# rfm12square.net
KiCad netlist of a schematic drawn in EAGLE
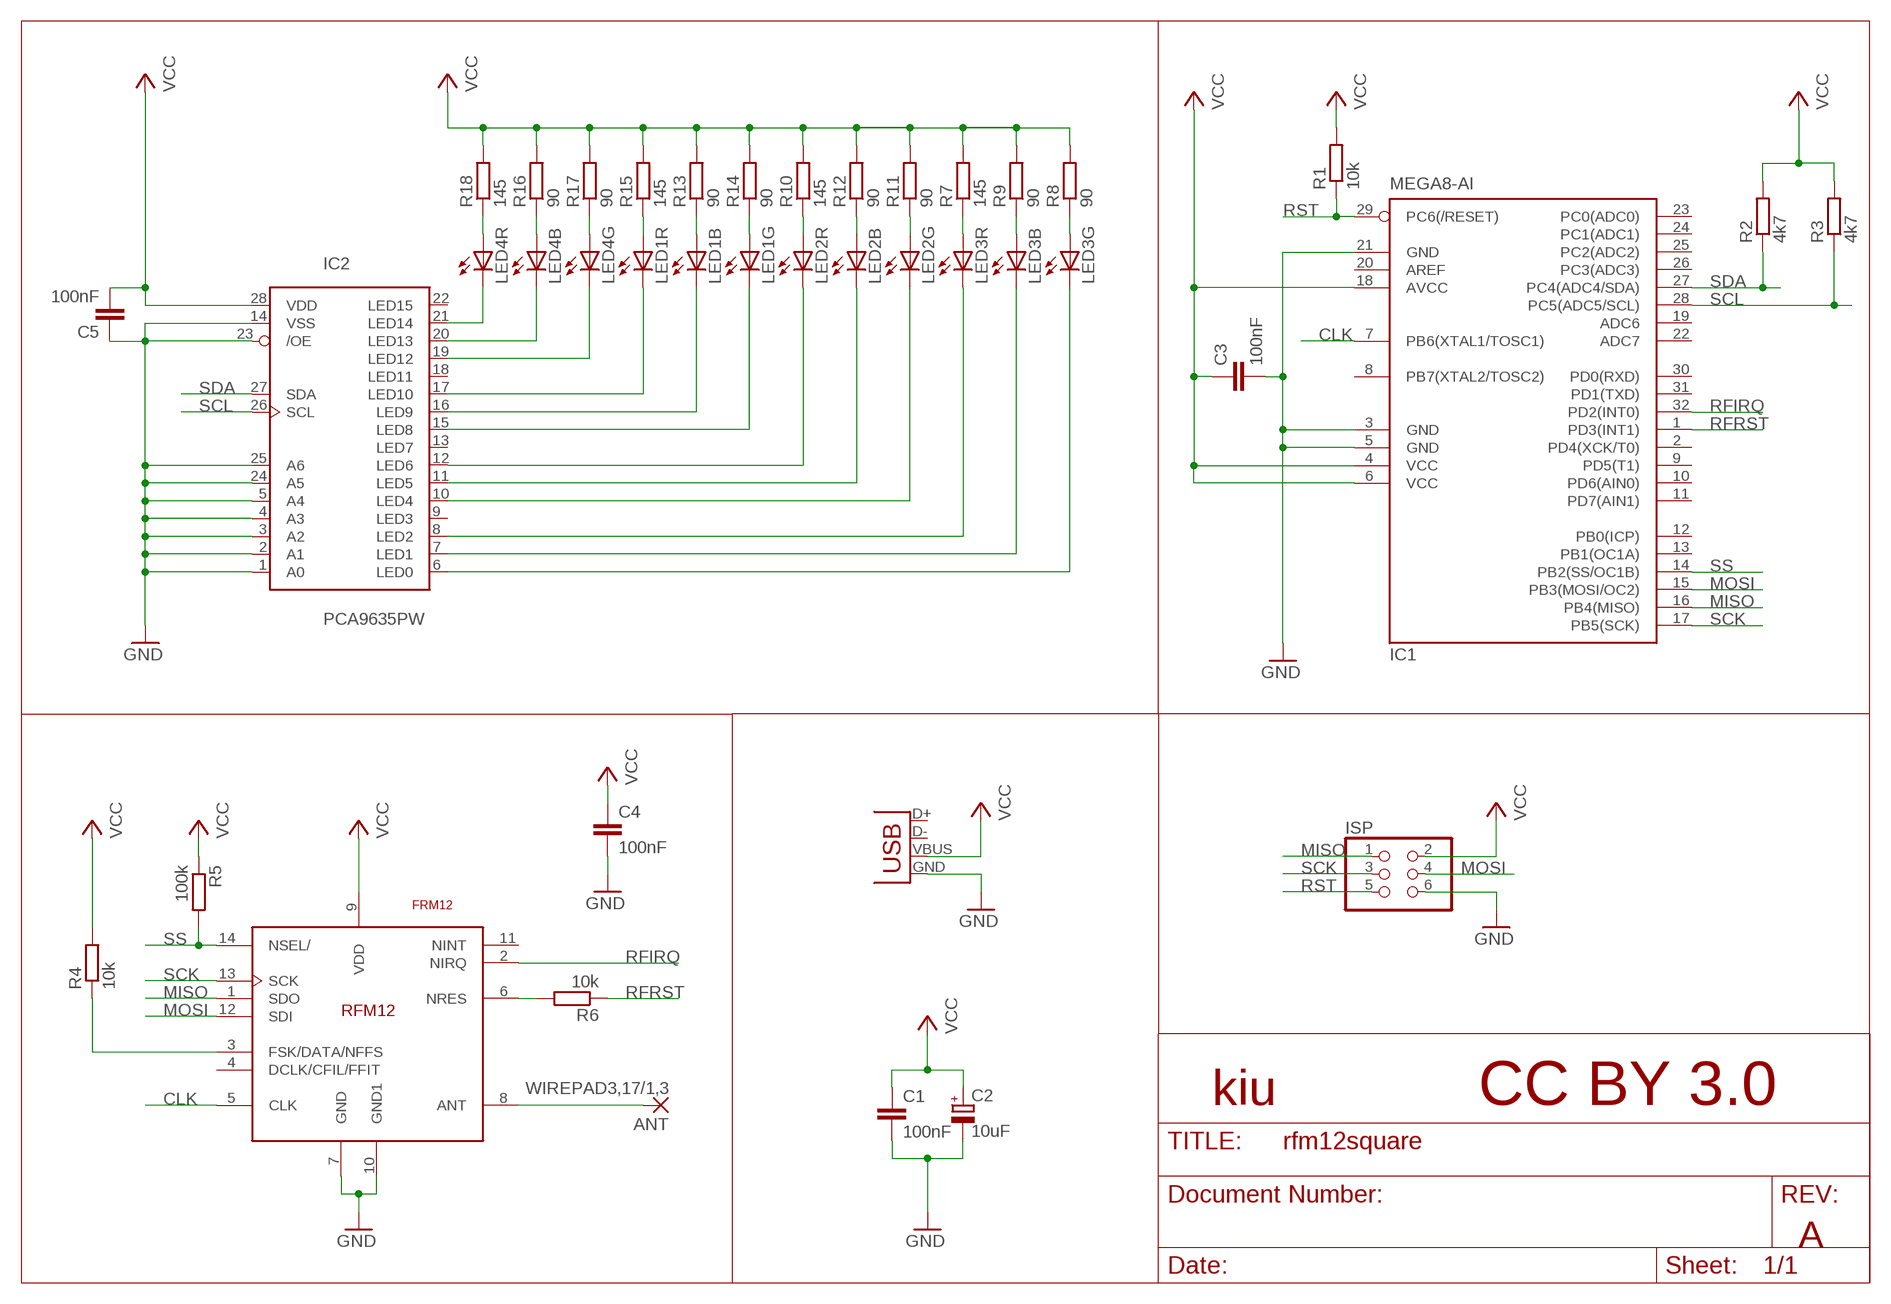
[diagram p0: schematic, sheet 1]

(export (version "E")
  (design (tool "Eeschema 10.0.6"))
  (components
    (comp (ref "ANT")
      (value "WIREPAD3,17/1,3")
      (footprint "eagle-import:3,17_1,3")
      (libsource (lib "eagle-import") (part "WIREPAD3,17/1,3"))
    )
    (comp (ref "C1")
      (value "100nF")
      (footprint "eagle-import:C0603")
      (libsource (lib "eagle-import") (part "C-EUC0603"))
    )
    (comp (ref "C2")
      (value "10uF")
      (footprint "eagle-import:CT3216")
      (libsource (lib "eagle-import") (part "CPOL-EUCT3216"))
    )
    (comp (ref "C3")
      (value "100nF")
      (footprint "eagle-import:C0603")
      (libsource (lib "eagle-import") (part "C-EUC0603"))
    )
    (comp (ref "C4")
      (value "100nF")
      (footprint "eagle-import:C0603")
      (libsource (lib "eagle-import") (part "C-EUC0603"))
    )
    (comp (ref "C5")
      (value "100nF")
      (footprint "eagle-import:C0603")
      (libsource (lib "eagle-import") (part "C-EUC0603"))
    )
    (comp (ref "IC1")
      (value "MEGA8-AI")
      (footprint "eagle-import:TQFP32-08")
      (fields (field (name "MPN") "ATMEGA8-16AU"))
      (libsource (lib "eagle-import") (part "MEGA8-AI"))
    )
    (comp (ref "IC2")
      (value "PCA9635PW")
      (footprint "eagle-import:TSSOP28")
      (libsource (lib "eagle-import") (part "PCA9635PW"))
    )
    (comp (ref "ISP")
      (value "PINHD-2X3")
      (footprint "eagle-import:2X03")
      (libsource (lib "eagle-import") (part "PINHD-2X3"))
    )
    (comp (ref "LED1")
      (value "MULTILED_LRTB_G6TG")
      (footprint "eagle-import:P-LCC-6_TOPLED")
      (libsource (lib "eagle-import") (part "MULTILED_LRTB_G6TG"))
    )
    (comp (ref "LED2")
      (value "MULTILED_LRTB_G6TG")
      (footprint "eagle-import:P-LCC-6_TOPLED")
      (libsource (lib "eagle-import") (part "MULTILED_LRTB_G6TG"))
    )
    (comp (ref "LED3")
      (value "MULTILED_LRTB_G6TG")
      (footprint "eagle-import:P-LCC-6_TOPLED")
      (libsource (lib "eagle-import") (part "MULTILED_LRTB_G6TG"))
    )
    (comp (ref "LED4")
      (value "MULTILED_LRTB_G6TG")
      (footprint "eagle-import:P-LCC-6_TOPLED")
      (libsource (lib "eagle-import") (part "MULTILED_LRTB_G6TG"))
    )
    (comp (ref "R1")
      (value "10k")
      (footprint "eagle-import:R0603")
      (libsource (lib "eagle-import") (part "R-EU_R0603"))
    )
    (comp (ref "R2")
      (value "4k7")
      (footprint "eagle-import:R0603")
      (libsource (lib "eagle-import") (part "R-EU_R0603"))
    )
    (comp (ref "R3")
      (value "4k7")
      (footprint "eagle-import:R0603")
      (libsource (lib "eagle-import") (part "R-EU_R0603"))
    )
    (comp (ref "R4")
      (value "10k")
      (footprint "eagle-import:R0603")
      (libsource (lib "eagle-import") (part "R-EU_R0603"))
    )
    (comp (ref "R5")
      (value "100k")
      (footprint "eagle-import:R0603")
      (libsource (lib "eagle-import") (part "R-EU_R0603"))
    )
    (comp (ref "R6")
      (value "10k")
      (footprint "eagle-import:R0603")
      (libsource (lib "eagle-import") (part "R-EU_R0603"))
    )
    (comp (ref "R7")
      (value "145")
      (footprint "eagle-import:R0603")
      (libsource (lib "eagle-import") (part "R-EU_R0603"))
    )
    (comp (ref "R8")
      (value "90")
      (footprint "eagle-import:R0603")
      (libsource (lib "eagle-import") (part "R-EU_R0603"))
    )
    (comp (ref "R9")
      (value "90")
      (footprint "eagle-import:R0603")
      (libsource (lib "eagle-import") (part "R-EU_R0603"))
    )
    (comp (ref "R10")
      (value "145")
      (footprint "eagle-import:R0603")
      (libsource (lib "eagle-import") (part "R-EU_R0603"))
    )
    (comp (ref "R11")
      (value "90")
      (footprint "eagle-import:R0603")
      (libsource (lib "eagle-import") (part "R-EU_R0603"))
    )
    (comp (ref "R12")
      (value "90")
      (footprint "eagle-import:R0603")
      (libsource (lib "eagle-import") (part "R-EU_R0603"))
    )
    (comp (ref "R13")
      (value "90")
      (footprint "eagle-import:R0603")
      (libsource (lib "eagle-import") (part "R-EU_R0603"))
    )
    (comp (ref "R14")
      (value "90")
      (footprint "eagle-import:R0603")
      (libsource (lib "eagle-import") (part "R-EU_R0603"))
    )
    (comp (ref "R15")
      (value "145")
      (footprint "eagle-import:R0603")
      (libsource (lib "eagle-import") (part "R-EU_R0603"))
    )
    (comp (ref "R16")
      (value "90")
      (footprint "eagle-import:R0603")
      (libsource (lib "eagle-import") (part "R-EU_R0603"))
    )
    (comp (ref "R17")
      (value "90")
      (footprint "eagle-import:R0603")
      (libsource (lib "eagle-import") (part "R-EU_R0603"))
    )
    (comp (ref "R18")
      (value "145")
      (footprint "eagle-import:R0603")
      (libsource (lib "eagle-import") (part "R-EU_R0603"))
    )
    (comp (ref "U$1")
      (value "FRM12")
      (footprint "eagle-import:RFM12")
      (libsource (lib "eagle-import") (part "FRM12"))
    )
    (comp (ref "X1")
      (value "USB-MICROB")
      (footprint "eagle-import:USB-MICROB")
      (libsource (lib "eagle-import") (part "USB-MICROB"))
    )
  )
  (nets
    (net (code "1") (name "/CLK") (class "Default")
      (node (ref "IC1") (pin "7") (pinfunction "PB6(XTAL1/TOSC1)_7") (pintype "bidirectional"))
      (node (ref "U$1") (pin "5") (pinfunction "CLK_5") (pintype "output"))
    )
    (net (code "2") (name "/MISO") (class "Default")
      (node (ref "IC1") (pin "16") (pinfunction "PB4(MISO)_16") (pintype "bidirectional"))
      (node (ref "ISP") (pin "1") (pinfunction "1_1") (pintype "passive"))
      (node (ref "U$1") (pin "1") (pinfunction "SDO_1") (pintype "output"))
    )
    (net (code "3") (name "/MOSI") (class "Default")
      (node (ref "IC1") (pin "15") (pinfunction "PB3(MOSI/OC2)_15") (pintype "bidirectional"))
      (node (ref "ISP") (pin "4") (pinfunction "4_4") (pintype "passive"))
      (node (ref "U$1") (pin "12") (pinfunction "SDI_12") (pintype "input"))
    )
    (net (code "4") (name "/RFIRQ") (class "Default")
      (node (ref "IC1") (pin "32") (pinfunction "PD2(INT0)_32") (pintype "bidirectional"))
      (node (ref "U$1") (pin "2") (pinfunction "NIRQ_2") (pintype "output"))
    )
    (net (code "5") (name "/RFRST") (class "Default")
      (node (ref "IC1") (pin "1") (pinfunction "PD3(INT1)_1") (pintype "bidirectional"))
      (node (ref "R6") (pin "1") (pinfunction "1_1") (pintype "passive"))
    )
    (net (code "6") (name "/RST") (class "Default")
      (node (ref "IC1") (pin "29") (pinfunction "PC6(/RESET)_29") (pintype "bidirectional"))
      (node (ref "ISP") (pin "5") (pinfunction "5_5") (pintype "passive"))
      (node (ref "R1") (pin "1") (pinfunction "1_1") (pintype "passive"))
    )
    (net (code "7") (name "/SCK") (class "Default")
      (node (ref "IC1") (pin "17") (pinfunction "PB5(SCK)_17") (pintype "bidirectional"))
      (node (ref "ISP") (pin "3") (pinfunction "3_3") (pintype "passive"))
      (node (ref "U$1") (pin "13") (pinfunction "SCK_13") (pintype "input"))
    )
    (net (code "8") (name "/SCL") (class "Default")
      (node (ref "IC1") (pin "28") (pinfunction "PC5(ADC5/SCL)_28") (pintype "bidirectional"))
      (node (ref "IC2") (pin "26") (pinfunction "SCL_26") (pintype "input"))
      (node (ref "R3") (pin "1") (pinfunction "1_1") (pintype "passive"))
    )
    (net (code "9") (name "/SDA") (class "Default")
      (node (ref "IC1") (pin "27") (pinfunction "PC4(ADC4/SDA)_27") (pintype "bidirectional"))
      (node (ref "IC2") (pin "27") (pinfunction "SDA_27") (pintype "bidirectional"))
      (node (ref "R2") (pin "1") (pinfunction "1_1") (pintype "passive"))
    )
    (net (code "10") (name "/SS") (class "Default")
      (node (ref "IC1") (pin "14") (pinfunction "PB2(SS/OC1B)_14") (pintype "bidirectional"))
      (node (ref "R5") (pin "2") (pinfunction "2_2") (pintype "passive"))
      (node (ref "U$1") (pin "14") (pinfunction "NSEL/_14") (pintype "input"))
    )
    (net (code "11") (name "GND") (class "Default")
      (node (ref "C1") (pin "2") (pinfunction "2_2") (pintype "passive"))
      (node (ref "C2") (pin "-") (pinfunction "-_-") (pintype "passive"))
      (node (ref "C3") (pin "2") (pinfunction "2_2") (pintype "passive"))
      (node (ref "C4") (pin "2") (pinfunction "2_2") (pintype "passive"))
      (node (ref "C5") (pin "1") (pinfunction "1_1") (pintype "passive"))
      (node (ref "IC1") (pin "21") (pinfunction "GND_21") (pintype "power_in"))
      (node (ref "IC1") (pin "3") (pinfunction "GND_3") (pintype "power_in"))
      (node (ref "IC1") (pin "5") (pinfunction "GND_5") (pintype "power_in"))
      (node (ref "IC2") (pin "1") (pinfunction "A0_1") (pintype "input"))
      (node (ref "IC2") (pin "14") (pinfunction "VSS_14") (pintype "power_in"))
      (node (ref "IC2") (pin "2") (pinfunction "A1_2") (pintype "input"))
      (node (ref "IC2") (pin "23") (pinfunction "/OE_23") (pintype "input"))
      (node (ref "IC2") (pin "24") (pinfunction "A5_24") (pintype "input"))
      (node (ref "IC2") (pin "25") (pinfunction "A6_25") (pintype "input"))
      (node (ref "IC2") (pin "3") (pinfunction "A2_3") (pintype "input"))
      (node (ref "IC2") (pin "4") (pinfunction "A3_4") (pintype "input"))
      (node (ref "IC2") (pin "5") (pinfunction "A4_5") (pintype "input"))
      (node (ref "ISP") (pin "6") (pinfunction "6_6") (pintype "passive"))
      (node (ref "U$1") (pin "10") (pinfunction "GND1_10") (pintype "passive"))
      (node (ref "U$1") (pin "7") (pinfunction "GND_7") (pintype "passive"))
      (node (ref "X1") (pin "GND") (pinfunction "GND_GND") (pintype "bidirectional"))
    )
    (net (code "12") (name "Net-(ANT-P)") (class "Default")
      (node (ref "ANT") (pin "1") (pinfunction "P_1") (pintype "passive"))
      (node (ref "U$1") (pin "8") (pinfunction "ANT_8") (pintype "bidirectional"))
    )
    (net (code "13") (name "Net-(IC2-LED0)") (class "Default")
      (node (ref "IC2") (pin "6") (pinfunction "LED0_6") (pintype "output"))
      (node (ref "LED3") (pin "C2") (pinfunction "C_C2") (pintype "passive"))
    )
    (net (code "14") (name "Net-(IC2-LED1)") (class "Default")
      (node (ref "IC2") (pin "7") (pinfunction "LED1_7") (pintype "output"))
      (node (ref "LED3") (pin "C3") (pinfunction "C_C3") (pintype "passive"))
    )
    (net (code "15") (name "Net-(IC2-LED2)") (class "Default")
      (node (ref "IC2") (pin "8") (pinfunction "LED2_8") (pintype "output"))
      (node (ref "LED3") (pin "C1") (pinfunction "C_C1") (pintype "passive"))
    )
    (net (code "16") (name "Net-(IC2-LED4)") (class "Default")
      (node (ref "IC2") (pin "10") (pinfunction "LED4_10") (pintype "output"))
      (node (ref "LED2") (pin "C2") (pinfunction "C_C2") (pintype "passive"))
    )
    (net (code "17") (name "Net-(IC2-LED5)") (class "Default")
      (node (ref "IC2") (pin "11") (pinfunction "LED5_11") (pintype "output"))
      (node (ref "LED2") (pin "C3") (pinfunction "C_C3") (pintype "passive"))
    )
    (net (code "18") (name "Net-(IC2-LED6)") (class "Default")
      (node (ref "IC2") (pin "12") (pinfunction "LED6_12") (pintype "output"))
      (node (ref "LED2") (pin "C1") (pinfunction "C_C1") (pintype "passive"))
    )
    (net (code "19") (name "Net-(IC2-LED8)") (class "Default")
      (node (ref "IC2") (pin "15") (pinfunction "LED8_15") (pintype "output"))
      (node (ref "LED1") (pin "C2") (pinfunction "C_C2") (pintype "passive"))
    )
    (net (code "20") (name "Net-(IC2-LED9)") (class "Default")
      (node (ref "IC2") (pin "16") (pinfunction "LED9_16") (pintype "output"))
      (node (ref "LED1") (pin "C3") (pinfunction "C_C3") (pintype "passive"))
    )
    (net (code "21") (name "Net-(IC2-LED10)") (class "Default")
      (node (ref "IC2") (pin "17") (pinfunction "LED10_17") (pintype "output"))
      (node (ref "LED1") (pin "C1") (pinfunction "C_C1") (pintype "passive"))
    )
    (net (code "22") (name "Net-(IC2-LED12)") (class "Default")
      (node (ref "IC2") (pin "19") (pinfunction "LED12_19") (pintype "output"))
      (node (ref "LED4") (pin "C2") (pinfunction "C_C2") (pintype "passive"))
    )
    (net (code "23") (name "Net-(IC2-LED13)") (class "Default")
      (node (ref "IC2") (pin "20") (pinfunction "LED13_20") (pintype "output"))
      (node (ref "LED4") (pin "C3") (pinfunction "C_C3") (pintype "passive"))
    )
    (net (code "24") (name "Net-(IC2-LED14)") (class "Default")
      (node (ref "IC2") (pin "21") (pinfunction "LED14_21") (pintype "output"))
      (node (ref "LED4") (pin "C1") (pinfunction "C_C1") (pintype "passive"))
    )
    (net (code "25") (name "Net-(LED1A-A)") (class "Default")
      (node (ref "LED1") (pin "A3") (pinfunction "A_A3") (pintype "passive"))
      (node (ref "R13") (pin "1") (pinfunction "1_1") (pintype "passive"))
    )
    (net (code "26") (name "Net-(LED1B-A)") (class "Default")
      (node (ref "LED1") (pin "A2") (pinfunction "A_A2") (pintype "passive"))
      (node (ref "R14") (pin "1") (pinfunction "1_1") (pintype "passive"))
    )
    (net (code "27") (name "Net-(LED1C-A)") (class "Default")
      (node (ref "LED1") (pin "A1") (pinfunction "A_A1") (pintype "passive"))
      (node (ref "R15") (pin "1") (pinfunction "1_1") (pintype "passive"))
    )
    (net (code "28") (name "Net-(LED2A-A)") (class "Default")
      (node (ref "LED2") (pin "A3") (pinfunction "A_A3") (pintype "passive"))
      (node (ref "R12") (pin "1") (pinfunction "1_1") (pintype "passive"))
    )
    (net (code "29") (name "Net-(LED2B-A)") (class "Default")
      (node (ref "LED2") (pin "A2") (pinfunction "A_A2") (pintype "passive"))
      (node (ref "R11") (pin "1") (pinfunction "1_1") (pintype "passive"))
    )
    (net (code "30") (name "Net-(LED2C-A)") (class "Default")
      (node (ref "LED2") (pin "A1") (pinfunction "A_A1") (pintype "passive"))
      (node (ref "R10") (pin "1") (pinfunction "1_1") (pintype "passive"))
    )
    (net (code "31") (name "Net-(LED3A-A)") (class "Default")
      (node (ref "LED3") (pin "A3") (pinfunction "A_A3") (pintype "passive"))
      (node (ref "R9") (pin "1") (pinfunction "1_1") (pintype "passive"))
    )
    (net (code "32") (name "Net-(LED3B-A)") (class "Default")
      (node (ref "LED3") (pin "A2") (pinfunction "A_A2") (pintype "passive"))
      (node (ref "R8") (pin "1") (pinfunction "1_1") (pintype "passive"))
    )
    (net (code "33") (name "Net-(LED3C-A)") (class "Default")
      (node (ref "LED3") (pin "A1") (pinfunction "A_A1") (pintype "passive"))
      (node (ref "R7") (pin "1") (pinfunction "1_1") (pintype "passive"))
    )
    (net (code "34") (name "Net-(LED4A-A)") (class "Default")
      (node (ref "LED4") (pin "A3") (pinfunction "A_A3") (pintype "passive"))
      (node (ref "R16") (pin "1") (pinfunction "1_1") (pintype "passive"))
    )
    (net (code "35") (name "Net-(LED4B-A)") (class "Default")
      (node (ref "LED4") (pin "A2") (pinfunction "A_A2") (pintype "passive"))
      (node (ref "R17") (pin "1") (pinfunction "1_1") (pintype "passive"))
    )
    (net (code "36") (name "Net-(LED4C-A)") (class "Default")
      (node (ref "LED4") (pin "A1") (pinfunction "A_A1") (pintype "passive"))
      (node (ref "R18") (pin "1") (pinfunction "1_1") (pintype "passive"))
    )
    (net (code "37") (name "Net-(U$1-FSK{slash}DATA{slash}NFFS)") (class "Default")
      (node (ref "R4") (pin "1") (pinfunction "1_1") (pintype "passive"))
      (node (ref "U$1") (pin "3") (pinfunction "FSK/DATA/NFFS_3") (pintype "bidirectional"))
    )
    (net (code "38") (name "Net-(U$1-NRES)") (class "Default")
      (node (ref "R6") (pin "2") (pinfunction "2_2") (pintype "passive"))
      (node (ref "U$1") (pin "6") (pinfunction "NRES_6") (pintype "bidirectional"))
    )
    (net (code "39") (name "VCC") (class "Default")
      (node (ref "C1") (pin "1") (pinfunction "1_1") (pintype "passive"))
      (node (ref "C2") (pin "+") (pinfunction "+_+") (pintype "passive"))
      (node (ref "C3") (pin "1") (pinfunction "1_1") (pintype "passive"))
      (node (ref "C4") (pin "1") (pinfunction "1_1") (pintype "passive"))
      (node (ref "C5") (pin "2") (pinfunction "2_2") (pintype "passive"))
      (node (ref "IC1") (pin "18") (pinfunction "AVCC_18") (pintype "power_in"))
      (node (ref "IC1") (pin "4") (pinfunction "VCC_4") (pintype "power_in"))
      (node (ref "IC1") (pin "6") (pinfunction "VCC_6") (pintype "power_in"))
      (node (ref "IC2") (pin "28") (pinfunction "VDD_28") (pintype "power_in"))
      (node (ref "ISP") (pin "2") (pinfunction "2_2") (pintype "passive"))
      (node (ref "R1") (pin "2") (pinfunction "2_2") (pintype "passive"))
      (node (ref "R10") (pin "2") (pinfunction "2_2") (pintype "passive"))
      (node (ref "R11") (pin "2") (pinfunction "2_2") (pintype "passive"))
      (node (ref "R12") (pin "2") (pinfunction "2_2") (pintype "passive"))
      (node (ref "R13") (pin "2") (pinfunction "2_2") (pintype "passive"))
      (node (ref "R14") (pin "2") (pinfunction "2_2") (pintype "passive"))
      (node (ref "R15") (pin "2") (pinfunction "2_2") (pintype "passive"))
      (node (ref "R16") (pin "2") (pinfunction "2_2") (pintype "passive"))
      (node (ref "R17") (pin "2") (pinfunction "2_2") (pintype "passive"))
      (node (ref "R18") (pin "2") (pinfunction "2_2") (pintype "passive"))
      (node (ref "R2") (pin "2") (pinfunction "2_2") (pintype "passive"))
      (node (ref "R3") (pin "2") (pinfunction "2_2") (pintype "passive"))
      (node (ref "R4") (pin "2") (pinfunction "2_2") (pintype "passive"))
      (node (ref "R5") (pin "1") (pinfunction "1_1") (pintype "passive"))
      (node (ref "R7") (pin "2") (pinfunction "2_2") (pintype "passive"))
      (node (ref "R8") (pin "2") (pinfunction "2_2") (pintype "passive"))
      (node (ref "R9") (pin "2") (pinfunction "2_2") (pintype "passive"))
      (node (ref "U$1") (pin "9") (pinfunction "VDD_9") (pintype "power_in"))
      (node (ref "X1") (pin "VBUS") (pinfunction "VBUS_VBUS") (pintype "bidirectional"))
    )
    (net (code "40") (name "unconnected-(IC1-ADC6-Pad19)") (class "Default")
      (node (ref "IC1") (pin "19") (pinfunction "ADC6_19") (pintype "bidirectional"))
    )
    (net (code "41") (name "unconnected-(IC1-ADC7-Pad22)") (class "Default")
      (node (ref "IC1") (pin "22") (pinfunction "ADC7_22") (pintype "bidirectional"))
    )
    (net (code "42") (name "unconnected-(IC1-AREF-Pad20)") (class "Default")
      (node (ref "IC1") (pin "20") (pinfunction "AREF_20") (pintype "passive"))
    )
    (net (code "43") (name "unconnected-(IC1-PB0(ICP)-Pad12)") (class "Default")
      (node (ref "IC1") (pin "12") (pinfunction "PB0(ICP)_12") (pintype "bidirectional"))
    )
    (net (code "44") (name "unconnected-(IC1-PB1(OC1A)-Pad13)") (class "Default")
      (node (ref "IC1") (pin "13") (pinfunction "PB1(OC1A)_13") (pintype "bidirectional"))
    )
    (net (code "45") (name "unconnected-(IC1-PB7(XTAL2{slash}TOSC2)-Pad8)") (class "Default")
      (node (ref "IC1") (pin "8") (pinfunction "PB7(XTAL2/TOSC2)_8") (pintype "bidirectional"))
    )
    (net (code "46") (name "unconnected-(IC1-PC0(ADC0)-Pad23)") (class "Default")
      (node (ref "IC1") (pin "23") (pinfunction "PC0(ADC0)_23") (pintype "bidirectional"))
    )
    (net (code "47") (name "unconnected-(IC1-PC1(ADC1)-Pad24)") (class "Default")
      (node (ref "IC1") (pin "24") (pinfunction "PC1(ADC1)_24") (pintype "bidirectional"))
    )
    (net (code "48") (name "unconnected-(IC1-PC2(ADC2)-Pad25)") (class "Default")
      (node (ref "IC1") (pin "25") (pinfunction "PC2(ADC2)_25") (pintype "bidirectional"))
    )
    (net (code "49") (name "unconnected-(IC1-PC3(ADC3)-Pad26)") (class "Default")
      (node (ref "IC1") (pin "26") (pinfunction "PC3(ADC3)_26") (pintype "bidirectional"))
    )
    (net (code "50") (name "unconnected-(IC1-PD0(RXD)-Pad30)") (class "Default")
      (node (ref "IC1") (pin "30") (pinfunction "PD0(RXD)_30") (pintype "bidirectional"))
    )
    (net (code "51") (name "unconnected-(IC1-PD1(TXD)-Pad31)") (class "Default")
      (node (ref "IC1") (pin "31") (pinfunction "PD1(TXD)_31") (pintype "bidirectional"))
    )
    (net (code "52") (name "unconnected-(IC1-PD4(XCK{slash}T0)-Pad2)") (class "Default")
      (node (ref "IC1") (pin "2") (pinfunction "PD4(XCK/T0)_2") (pintype "bidirectional"))
    )
    (net (code "53") (name "unconnected-(IC1-PD5(T1)-Pad9)") (class "Default")
      (node (ref "IC1") (pin "9") (pinfunction "PD5(T1)_9") (pintype "bidirectional"))
    )
    (net (code "54") (name "unconnected-(IC1-PD6(AIN0)-Pad10)") (class "Default")
      (node (ref "IC1") (pin "10") (pinfunction "PD6(AIN0)_10") (pintype "bidirectional"))
    )
    (net (code "55") (name "unconnected-(IC1-PD7(AIN1)-Pad11)") (class "Default")
      (node (ref "IC1") (pin "11") (pinfunction "PD7(AIN1)_11") (pintype "bidirectional"))
    )
    (net (code "56") (name "unconnected-(IC2-LED3-Pad9)") (class "Default")
      (node (ref "IC2") (pin "9") (pinfunction "LED3_9") (pintype "output"))
    )
    (net (code "57") (name "unconnected-(IC2-LED7-Pad13)") (class "Default")
      (node (ref "IC2") (pin "13") (pinfunction "LED7_13") (pintype "output"))
    )
    (net (code "58") (name "unconnected-(IC2-LED11-Pad18)") (class "Default")
      (node (ref "IC2") (pin "18") (pinfunction "LED11_18") (pintype "output"))
    )
    (net (code "59") (name "unconnected-(IC2-LED15-Pad22)") (class "Default")
      (node (ref "IC2") (pin "22") (pinfunction "LED15_22") (pintype "output"))
    )
    (net (code "60") (name "unconnected-(U$1-DCLK{slash}CFIL{slash}FFIT-Pad4)") (class "Default")
      (node (ref "U$1") (pin "4") (pinfunction "DCLK/CFIL/FFIT_4") (pintype "bidirectional"))
    )
    (net (code "61") (name "unconnected-(U$1-NINT-Pad11)") (class "Default")
      (node (ref "U$1") (pin "11") (pinfunction "NINT_11") (pintype "bidirectional"))
    )
    (net (code "62") (name "unconnected-(X1-PadD+)") (class "Default")
      (node (ref "X1") (pin "D+") (pinfunction "D+_D+") (pintype "bidirectional"))
    )
    (net (code "63") (name "unconnected-(X1-PadD-)") (class "Default")
      (node (ref "X1") (pin "D-") (pinfunction "D-_D-") (pintype "bidirectional"))
    )
  )
)
